# PowerSupply.net
KiCad netlist of a schematic drawn in Altium Designer
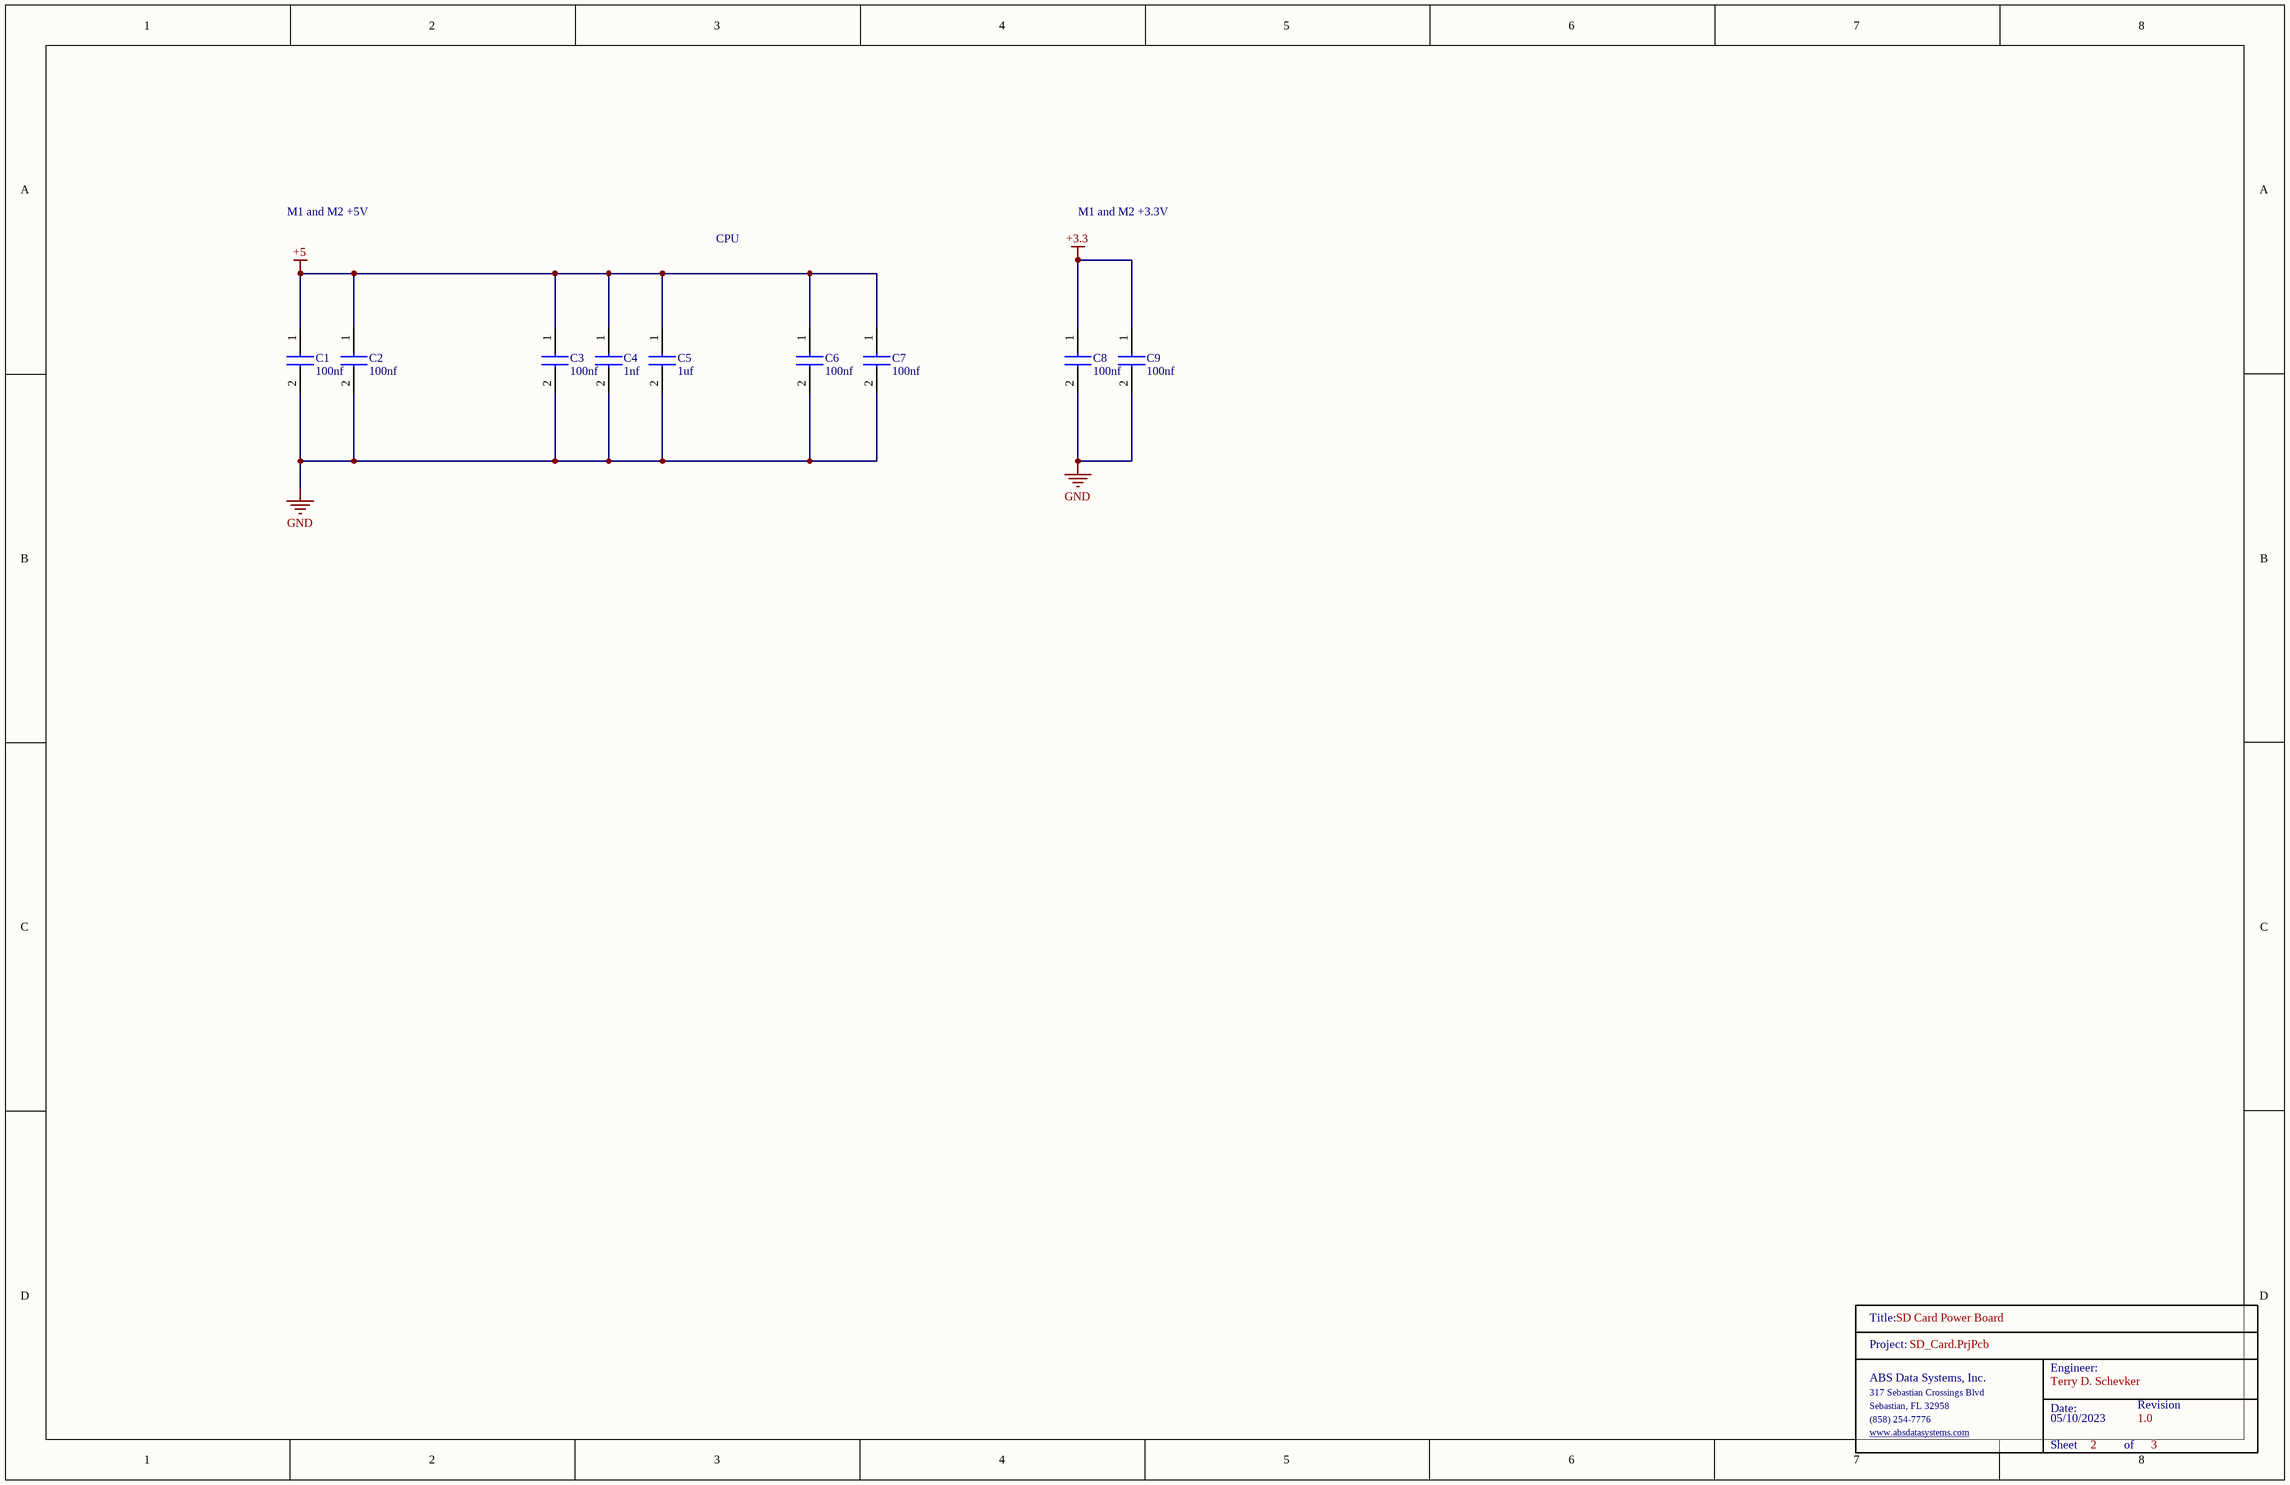
[diagram p0: PowerSupply.SchDoc]

(export (version "E")
  (design (tool "Eeschema 10.0.6"))
  (components
    (comp (ref "C1")
      (value "100nf")
      (footprint "0603")
      (description "Samsung Electro-Mechanics 0603 100nf")
      (libsource (lib "Capacitors") (part "CL10B104JB8NNNC"))
    )
    (comp (ref "C2")
      (value "100nf")
      (footprint "0603")
      (description "Samsung Electro-Mechanics 0603 100nf")
      (libsource (lib "Capacitors") (part "CL10B104JB8NNNC"))
    )
    (comp (ref "C3")
      (value "100nf")
      (footprint "0603")
      (description "Samsung Electro-Mechanics 0603 100nf")
      (libsource (lib "Capacitors") (part "CL10B104JB8NNNC"))
    )
    (comp (ref "C4")
      (value "1nf")
      (footprint "0603")
      (description "Samsung Electro-Mechanics 0603 1nf")
      (libsource (lib "Capacitors") (part "CL10B102KB8NNNL"))
    )
    (comp (ref "C5")
      (value "1uf")
      (footprint "0603")
      (description "Samsung Electro-Mechanics 0603 1uf")
      (libsource (lib "Capacitors") (part "CL10B105KA8NNNL"))
    )
    (comp (ref "C6")
      (value "100nf")
      (footprint "0603")
      (description "Samsung Electro-Mechanics 0603 100nf")
      (libsource (lib "Capacitors") (part "CL10B104JB8NNNC"))
    )
    (comp (ref "C7")
      (value "100nf")
      (footprint "0603")
      (description "Samsung Electro-Mechanics 0603 100nf")
      (libsource (lib "Capacitors") (part "CL10B104JB8NNNC"))
    )
    (comp (ref "C8")
      (value "100nf")
      (footprint "0603")
      (description "Samsung Electro-Mechanics 0603 100nf")
      (libsource (lib "Capacitors") (part "CL10B104JB8NNNC"))
    )
    (comp (ref "C9")
      (value "100nf")
      (footprint "0603")
      (description "Samsung Electro-Mechanics 0603 100nf")
      (libsource (lib "Capacitors") (part "CL10B104JB8NNNC"))
    )
    (comp (ref "TitleBlock_2") (value "TitleBlock") (libsource (lib "Misc") (part "TitleBlock")))
  )
  (nets
    (net (code "1") (name "+3.3") (class "Default")
      (node (ref "C8") (pin "1") (pinfunction "1_1") (pintype "passive"))
      (node (ref "C9") (pin "1") (pinfunction "1_1") (pintype "passive"))
    )
    (net (code "2") (name "+5") (class "Default")
      (node (ref "C1") (pin "1") (pinfunction "1_1") (pintype "passive"))
      (node (ref "C2") (pin "1") (pinfunction "1_1") (pintype "passive"))
      (node (ref "C3") (pin "1") (pinfunction "1_1") (pintype "passive"))
      (node (ref "C4") (pin "1") (pinfunction "1_1") (pintype "passive"))
      (node (ref "C5") (pin "1") (pinfunction "1_1") (pintype "passive"))
      (node (ref "C6") (pin "1") (pinfunction "1_1") (pintype "passive"))
      (node (ref "C7") (pin "1") (pinfunction "1_1") (pintype "passive"))
    )
    (net (code "3") (name "GND") (class "Default")
      (node (ref "C1") (pin "2") (pinfunction "2_2") (pintype "passive"))
      (node (ref "C2") (pin "2") (pinfunction "2_2") (pintype "passive"))
      (node (ref "C3") (pin "2") (pinfunction "2_2") (pintype "passive"))
      (node (ref "C4") (pin "2") (pinfunction "2_2") (pintype "passive"))
      (node (ref "C5") (pin "2") (pinfunction "2_2") (pintype "passive"))
      (node (ref "C6") (pin "2") (pinfunction "2_2") (pintype "passive"))
      (node (ref "C7") (pin "2") (pinfunction "2_2") (pintype "passive"))
      (node (ref "C8") (pin "2") (pinfunction "2_2") (pintype "passive"))
      (node (ref "C9") (pin "2") (pinfunction "2_2") (pintype "passive"))
    )
  )
)
